# BrillBox.net
KiCad netlist of a schematic drawn in EAGLE
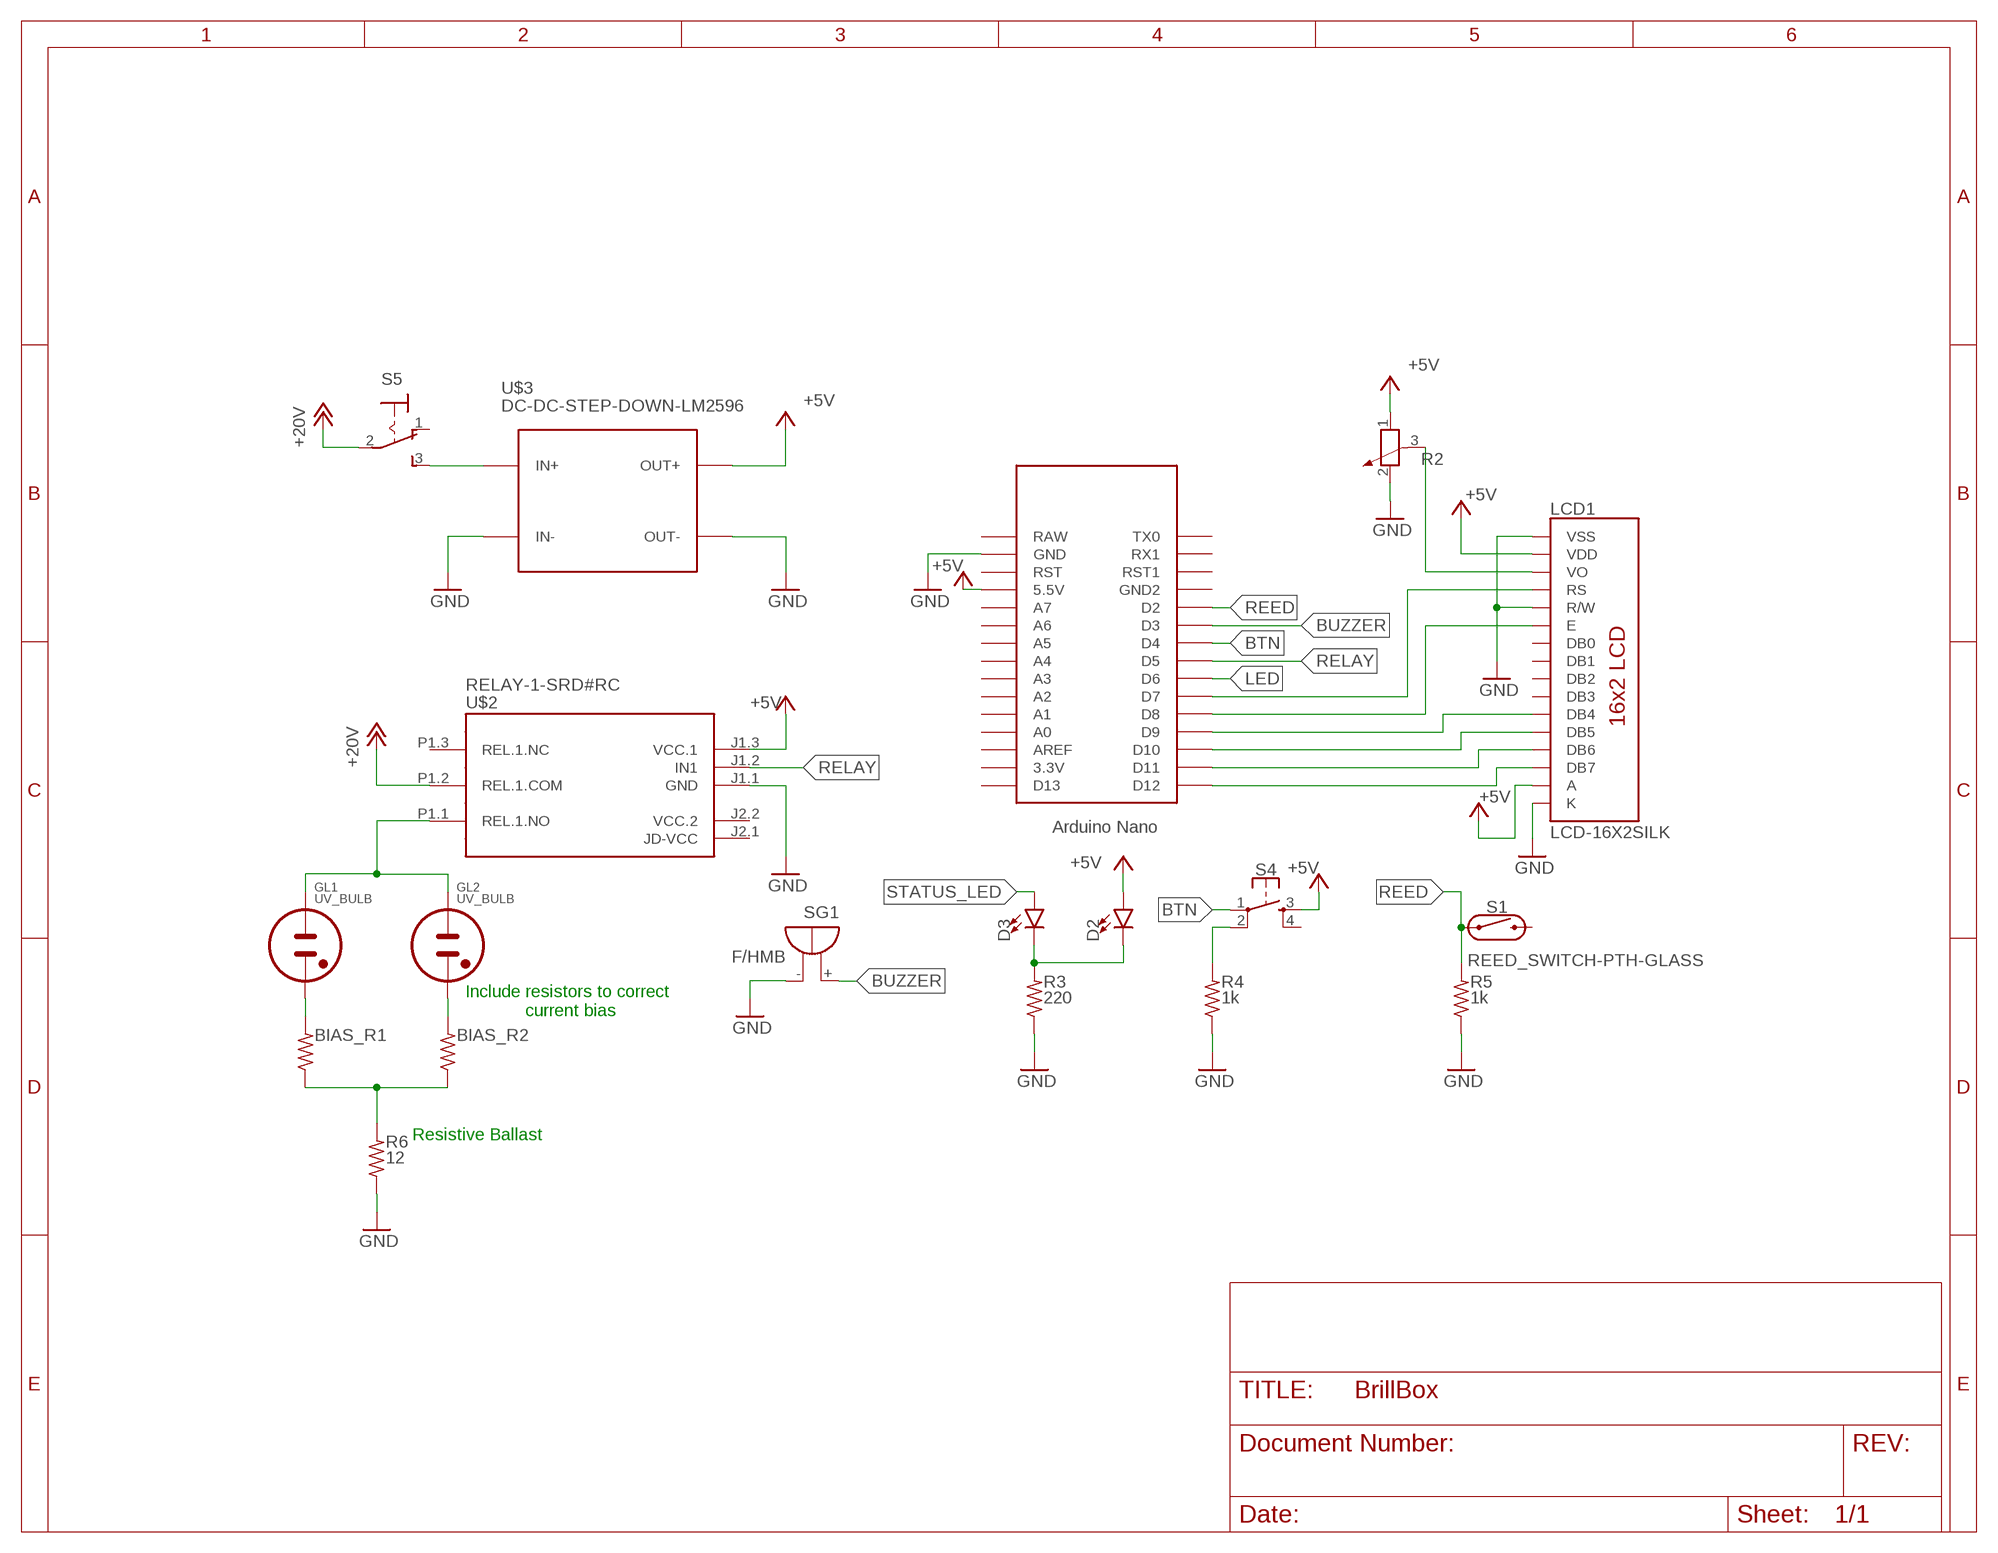
[diagram p0: schematic, sheet 1]

(export (version "E")
  (design (tool "Eeschema 10.0.6"))
  (components
    (comp (ref "BIAS_R1")
      (value "R-US_0207/12")
      (footprint "eagle-import:0207_12")
      (libsource (lib "eagle-import") (part "R-US_0207/12"))
    )
    (comp (ref "BIAS_R2")
      (value "R-US_0207/12")
      (footprint "eagle-import:0207_12")
      (libsource (lib "eagle-import") (part "R-US_0207/12"))
    )
    (comp (ref "D2")
      (value "LED5MM")
      (footprint "eagle-import:LED_5MM")
      (libsource (lib "eagle-import") (part "LED5MM"))
    )
    (comp (ref "D3")
      (value "LED5MM")
      (footprint "eagle-import:LED_5MM")
      (libsource (lib "eagle-import") (part "LED5MM"))
    )
    (comp (ref "GL1")
      (value "UV_BULB")
      (footprint "eagle-import:NE2-NEON-BULB-SMD")
      (libsource (lib "eagle-import") (part "NE2-NEON-BULB-SMD"))
    )
    (comp (ref "GL2")
      (value "UV_BULB")
      (footprint "eagle-import:NE2-NEON-BULB-SMD")
      (libsource (lib "eagle-import") (part "NE2-NEON-BULB-SMD"))
    )
    (comp (ref "LCD1")
      (value "LCD-16X2SILK")
      (footprint "eagle-import:LCD-16X2")
      (libsource (lib "eagle-import") (part "LCD-16X2SILK"))
    )
    (comp (ref "R2")
      (value "POTENTIOMETER_PT-10S")
      (footprint "eagle-import:PT-10S")
      (libsource (lib "eagle-import") (part "POTENTIOMETER_PT-10S"))
    )
    (comp (ref "R3")
      (value "220")
      (footprint "eagle-import:0207_12")
      (libsource (lib "eagle-import") (part "R-US_0207/12"))
    )
    (comp (ref "R4")
      (value "1k")
      (footprint "eagle-import:0207_12")
      (libsource (lib "eagle-import") (part "R-US_0207/12"))
    )
    (comp (ref "R5")
      (value "1k")
      (footprint "eagle-import:0207_12")
      (libsource (lib "eagle-import") (part "R-US_0207/12"))
    )
    (comp (ref "R6")
      (value "12")
      (footprint "eagle-import:0207_12")
      (libsource (lib "eagle-import") (part "R-US_0207/12"))
    )
    (comp (ref "S1")
      (value "REED_SWITCH-PTH-GLASS")
      (footprint "eagle-import:REED_SWITCH_GLASS")
      (libsource (lib "eagle-import") (part "REED_SWITCH-PTH-GLASS"))
    )
    (comp (ref "S4")
      (value "MOMENTARY-SWITCH-SPST-2-SMD-4.6X2.8MM")
      (footprint "eagle-import:TACTILE_SWITCH_SMD_4.6X2.8MM")
      (libsource (lib "eagle-import") (part "MOMENTARY-SWITCH-SPST-2-SMD-4.6X2.8MM"))
    )
    (comp (ref "S5")
      (value "M9040P")
      (footprint "eagle-import:M9040P")
      (libsource (lib "eagle-import") (part "M9040P"))
    )
    (comp (ref "SG1")
      (value "F/HMB")
      (footprint "eagle-import:F_HMB")
      (libsource (lib "eagle-import") (part "F/HMB"))
    )
    (comp (ref "U$1")
      (value "NANO")
      (footprint "eagle-import:NANO")
      (libsource (lib "eagle-import") (part "NANO"))
    )
    (comp (ref "U$2")
      (value "RELAY-1-SRD#RC")
      (footprint "eagle-import:RELAY-1-SRD#RC")
      (libsource (lib "eagle-import") (part "RELAY-1-SRD#RC"))
    )
    (comp (ref "U$3")
      (value "DC-DC-STEP-DOWN-LM2596")
      (footprint "eagle-import:DC-DC-STEP-DOWN-LM2596")
      (libsource (lib "eagle-import") (part "DC-DC-STEP-DOWN-LM2596"))
    )
  )
  (nets
    (net (code "1") (name "+5V") (class "Default")
      (node (ref "D2") (pin "A") (pinfunction "A_A") (pintype "passive"))
      (node (ref "LCD1") (pin "15") (pinfunction "A_15") (pintype "power_in"))
      (node (ref "LCD1") (pin "2") (pinfunction "VDD_2") (pintype "power_in"))
      (node (ref "R2") (pin "1") (pinfunction "1_1") (pintype "passive"))
      (node (ref "S4") (pin "3") (pinfunction "3_3") (pintype "passive"))
      (node (ref "U$1") (pin "5V") (pinfunction "5.5V_5V") (pintype "bidirectional"))
      (node (ref "U$2") (pin "J1.3") (pinfunction "VCC.1_J1.3") (pintype "power_in"))
      (node (ref "U$3") (pin "OUT+") (pinfunction "OUT+_OUT+") (pintype "bidirectional"))
    )
    (net (code "2") (name "+20V") (class "Default")
      (node (ref "S5") (pin "2") (pinfunction "P_2") (pintype "passive"))
      (node (ref "U$2") (pin "P1.2") (pinfunction "REL.1.COM_P1.2") (pintype "bidirectional"))
    )
    (net (code "3") (name "/VCC.2") (class "Default")
      (node (ref "U$2") (pin "J2.2") (pinfunction "VCC.2_J2.2") (pintype "power_in"))
    )
    (net (code "4") (name "BTN") (class "Default")
      (node (ref "S4") (pin "1") (pinfunction "1_1") (pintype "passive"))
      (node (ref "U$1") (pin "D4") (pinfunction "D4_D4") (pintype "bidirectional"))
    )
    (net (code "5") (name "BUZZER") (class "Default")
      (node (ref "SG1") (pin "+") (pinfunction "+_+") (pintype "passive"))
      (node (ref "U$1") (pin "D3") (pinfunction "D3_D3") (pintype "bidirectional"))
    )
    (net (code "6") (name "GND") (class "Default")
      (node (ref "LCD1") (pin "1") (pinfunction "VSS_1") (pintype "power_in"))
      (node (ref "LCD1") (pin "16") (pinfunction "K_16") (pintype "power_in"))
      (node (ref "LCD1") (pin "5") (pinfunction "R/W_5") (pintype "input"))
      (node (ref "R2") (pin "2") (pinfunction "2_2") (pintype "passive"))
      (node (ref "R3") (pin "1") (pinfunction "1_1") (pintype "passive"))
      (node (ref "R4") (pin "1") (pinfunction "1_1") (pintype "passive"))
      (node (ref "R5") (pin "1") (pinfunction "1_1") (pintype "passive"))
      (node (ref "R6") (pin "1") (pinfunction "1_1") (pintype "passive"))
      (node (ref "SG1") (pin "-") (pinfunction "-_-") (pintype "passive"))
      (node (ref "U$1") (pin "GND") (pinfunction "GND_GND") (pintype "bidirectional"))
      (node (ref "U$2") (pin "J1.1") (pinfunction "GND_J1.1") (pintype "power_in"))
      (node (ref "U$3") (pin "IN-") (pinfunction "IN-_IN-") (pintype "bidirectional"))
      (node (ref "U$3") (pin "OUT-") (pinfunction "OUT-_OUT-") (pintype "bidirectional"))
    )
    (net (code "7") (name "LED") (class "Default")
      (node (ref "U$1") (pin "D6") (pinfunction "D6_D6") (pintype "bidirectional"))
    )
    (net (code "8") (name "Net-(BIAS_R1-Pad1)") (class "Default")
      (node (ref "BIAS_R1") (pin "1") (pinfunction "1_1") (pintype "passive"))
      (node (ref "BIAS_R2") (pin "1") (pinfunction "1_1") (pintype "passive"))
      (node (ref "R6") (pin "2") (pinfunction "2_2") (pintype "passive"))
    )
    (net (code "9") (name "Net-(D2-C)") (class "Default")
      (node (ref "D2") (pin "K") (pinfunction "C_K") (pintype "passive"))
      (node (ref "D3") (pin "K") (pinfunction "C_K") (pintype "passive"))
      (node (ref "R3") (pin "2") (pinfunction "2_2") (pintype "passive"))
    )
    (net (code "10") (name "Net-(GL1-A)") (class "Default")
      (node (ref "GL1") (pin "1") (pinfunction "A_1") (pintype "passive"))
      (node (ref "GL2") (pin "1") (pinfunction "A_1") (pintype "passive"))
      (node (ref "U$2") (pin "P1.1") (pinfunction "REL.1.NO_P1.1") (pintype "bidirectional"))
    )
    (net (code "11") (name "Net-(GL1-A1)") (class "Default")
      (node (ref "BIAS_R1") (pin "2") (pinfunction "2_2") (pintype "passive"))
      (node (ref "GL1") (pin "2") (pinfunction "A1_2") (pintype "passive"))
    )
    (net (code "12") (name "Net-(GL2-A1)") (class "Default")
      (node (ref "BIAS_R2") (pin "2") (pinfunction "2_2") (pintype "passive"))
      (node (ref "GL2") (pin "2") (pinfunction "A1_2") (pintype "passive"))
    )
    (net (code "13") (name "Net-(LCD1-DB4)") (class "Default")
      (node (ref "LCD1") (pin "11") (pinfunction "DB4_11") (pintype "bidirectional"))
      (node (ref "U$1") (pin "D9") (pinfunction "D9_D9") (pintype "bidirectional"))
    )
    (net (code "14") (name "Net-(LCD1-DB5)") (class "Default")
      (node (ref "LCD1") (pin "12") (pinfunction "DB5_12") (pintype "bidirectional"))
      (node (ref "U$1") (pin "D10") (pinfunction "D10_D10") (pintype "bidirectional"))
    )
    (net (code "15") (name "Net-(LCD1-DB6)") (class "Default")
      (node (ref "LCD1") (pin "13") (pinfunction "DB6_13") (pintype "bidirectional"))
      (node (ref "U$1") (pin "D11") (pinfunction "D11_D11") (pintype "bidirectional"))
    )
    (net (code "16") (name "Net-(LCD1-DB7)") (class "Default")
      (node (ref "LCD1") (pin "14") (pinfunction "DB7_14") (pintype "bidirectional"))
      (node (ref "U$1") (pin "D12") (pinfunction "D12_D12") (pintype "bidirectional"))
    )
    (net (code "17") (name "Net-(LCD1-E)") (class "Default")
      (node (ref "LCD1") (pin "6") (pinfunction "E_6") (pintype "input"))
      (node (ref "U$1") (pin "D8") (pinfunction "D8_D8") (pintype "bidirectional"))
    )
    (net (code "18") (name "Net-(LCD1-RS)") (class "Default")
      (node (ref "LCD1") (pin "4") (pinfunction "RS_4") (pintype "input"))
      (node (ref "U$1") (pin "D7") (pinfunction "D7_D7") (pintype "bidirectional"))
    )
    (net (code "19") (name "Net-(LCD1-VO)") (class "Default")
      (node (ref "LCD1") (pin "3") (pinfunction "VO_3") (pintype "bidirectional"))
      (node (ref "R2") (pin "3") (pinfunction "3_3") (pintype "passive"))
    )
    (net (code "20") (name "Net-(R4-Pad2)") (class "Default")
      (node (ref "R4") (pin "2") (pinfunction "2_2") (pintype "passive"))
      (node (ref "S4") (pin "2") (pinfunction "2_2") (pintype "passive"))
    )
    (net (code "21") (name "Net-(S5-S)") (class "Default")
      (node (ref "S5") (pin "3") (pinfunction "S_3") (pintype "passive"))
      (node (ref "U$3") (pin "IN+") (pinfunction "IN+_IN+") (pintype "bidirectional"))
    )
    (net (code "22") (name "REED") (class "Default")
      (node (ref "R5") (pin "2") (pinfunction "2_2") (pintype "passive"))
      (node (ref "S1") (pin "P$1") (pinfunction "1_P$1") (pintype "passive"))
      (node (ref "U$1") (pin "D2") (pinfunction "D2_D2") (pintype "bidirectional"))
    )
    (net (code "23") (name "RELAY") (class "Default")
      (node (ref "U$1") (pin "D5") (pinfunction "D5_D5") (pintype "bidirectional"))
      (node (ref "U$2") (pin "J1.2") (pinfunction "IN1_J1.2") (pintype "bidirectional"))
    )
    (net (code "24") (name "STATUS_LED") (class "Default")
      (node (ref "D3") (pin "A") (pinfunction "A_A") (pintype "passive"))
    )
    (net (code "25") (name "unconnected-(LCD1-DB0-Pad7)") (class "Default")
      (node (ref "LCD1") (pin "7") (pinfunction "DB0_7") (pintype "bidirectional"))
    )
    (net (code "26") (name "unconnected-(LCD1-DB1-Pad8)") (class "Default")
      (node (ref "LCD1") (pin "8") (pinfunction "DB1_8") (pintype "bidirectional"))
    )
    (net (code "27") (name "unconnected-(LCD1-DB2-Pad9)") (class "Default")
      (node (ref "LCD1") (pin "9") (pinfunction "DB2_9") (pintype "bidirectional"))
    )
    (net (code "28") (name "unconnected-(LCD1-DB3-Pad10)") (class "Default")
      (node (ref "LCD1") (pin "10") (pinfunction "DB3_10") (pintype "bidirectional"))
    )
    (net (code "29") (name "unconnected-(S1-2-PadP$2)") (class "Default")
      (node (ref "S1") (pin "P$2") (pinfunction "2_P$2") (pintype "passive"))
    )
    (net (code "30") (name "unconnected-(S4-Pad4)") (class "Default")
      (node (ref "S4") (pin "4") (pinfunction "4_4") (pintype "passive"))
    )
    (net (code "31") (name "unconnected-(S5-O-Pad1)") (class "Default")
      (node (ref "S5") (pin "1") (pinfunction "O_1") (pintype "passive"))
    )
    (net (code "32") (name "unconnected-(U$1-GND2-PadGND1)") (class "Default")
      (node (ref "U$1") (pin "GND1") (pinfunction "GND2_GND1") (pintype "bidirectional"))
    )
    (net (code "33") (name "unconnected-(U$1-Pad3.3V)") (class "Default")
      (node (ref "U$1") (pin "3.3V") (pinfunction "3.3V_3.3V") (pintype "bidirectional"))
    )
    (net (code "34") (name "unconnected-(U$1-PadA0)") (class "Default")
      (node (ref "U$1") (pin "A0") (pinfunction "A0_A0") (pintype "bidirectional"))
    )
    (net (code "35") (name "unconnected-(U$1-PadA1)") (class "Default")
      (node (ref "U$1") (pin "A1") (pinfunction "A1_A1") (pintype "bidirectional"))
    )
    (net (code "36") (name "unconnected-(U$1-PadA2)") (class "Default")
      (node (ref "U$1") (pin "A2") (pinfunction "A2_A2") (pintype "bidirectional"))
    )
    (net (code "37") (name "unconnected-(U$1-PadA3)") (class "Default")
      (node (ref "U$1") (pin "A3") (pinfunction "A3_A3") (pintype "bidirectional"))
    )
    (net (code "38") (name "unconnected-(U$1-PadA4)") (class "Default")
      (node (ref "U$1") (pin "A4") (pinfunction "A4_A4") (pintype "bidirectional"))
    )
    (net (code "39") (name "unconnected-(U$1-PadA5)") (class "Default")
      (node (ref "U$1") (pin "A5") (pinfunction "A5_A5") (pintype "bidirectional"))
    )
    (net (code "40") (name "unconnected-(U$1-PadA6)") (class "Default")
      (node (ref "U$1") (pin "A6") (pinfunction "A6_A6") (pintype "bidirectional"))
    )
    (net (code "41") (name "unconnected-(U$1-PadA7)") (class "Default")
      (node (ref "U$1") (pin "A7") (pinfunction "A7_A7") (pintype "bidirectional"))
    )
    (net (code "42") (name "unconnected-(U$1-PadAREF)") (class "Default")
      (node (ref "U$1") (pin "AREF") (pinfunction "AREF_AREF") (pintype "bidirectional"))
    )
    (net (code "43") (name "unconnected-(U$1-PadD13)") (class "Default")
      (node (ref "U$1") (pin "D13") (pinfunction "D13_D13") (pintype "bidirectional"))
    )
    (net (code "44") (name "unconnected-(U$1-PadICSP1)") (class "Default")
      (node (ref "U$1") (pin "ICSP1") (pinfunction "ICSP1_ICSP1") (pintype "bidirectional"))
    )
    (net (code "45") (name "unconnected-(U$1-PadICSP2)") (class "Default")
      (node (ref "U$1") (pin "ICSP2") (pinfunction "ICSP2_ICSP2") (pintype "bidirectional"))
    )
    (net (code "46") (name "unconnected-(U$1-PadICSP3)") (class "Default")
      (node (ref "U$1") (pin "ICSP3") (pinfunction "ICSP3_ICSP3") (pintype "bidirectional"))
    )
    (net (code "47") (name "unconnected-(U$1-PadICSP4)") (class "Default")
      (node (ref "U$1") (pin "ICSP4") (pinfunction "ICSP4_ICSP4") (pintype "bidirectional"))
    )
    (net (code "48") (name "unconnected-(U$1-PadICSP5)") (class "Default")
      (node (ref "U$1") (pin "ICSP5") (pinfunction "ICSP5_ICSP5") (pintype "bidirectional"))
    )
    (net (code "49") (name "unconnected-(U$1-PadICSP6)") (class "Default")
      (node (ref "U$1") (pin "ICSP6") (pinfunction "ICSP6_ICSP6") (pintype "bidirectional"))
    )
    (net (code "50") (name "unconnected-(U$1-PadRAW)") (class "Default")
      (node (ref "U$1") (pin "RAW") (pinfunction "RAW_RAW") (pintype "bidirectional"))
    )
    (net (code "51") (name "unconnected-(U$1-PadRST)") (class "Default")
      (node (ref "U$1") (pin "RST") (pinfunction "RST_RST") (pintype "bidirectional"))
    )
    (net (code "52") (name "unconnected-(U$1-PadRST1)") (class "Default")
      (node (ref "U$1") (pin "RST1") (pinfunction "RST1_RST1") (pintype "bidirectional"))
    )
    (net (code "53") (name "unconnected-(U$1-PadRX1)") (class "Default")
      (node (ref "U$1") (pin "RX1") (pinfunction "RX1_RX1") (pintype "bidirectional"))
    )
    (net (code "54") (name "unconnected-(U$1-PadTX0)") (class "Default")
      (node (ref "U$1") (pin "TX0") (pinfunction "TX0_TX0") (pintype "bidirectional"))
    )
    (net (code "55") (name "unconnected-(U$2-JD-VCC-PadJ2.1)") (class "Default")
      (node (ref "U$2") (pin "J2.1") (pinfunction "JD-VCC_J2.1") (pintype "bidirectional"))
    )
    (net (code "56") (name "unconnected-(U$2-REL.1.NC-PadP1.3)") (class "Default")
      (node (ref "U$2") (pin "P1.3") (pinfunction "REL.1.NC_P1.3") (pintype "bidirectional"))
    )
  )
)
